# 4_PowerSupplie.net
KiCad netlist of a schematic drawn in Altium Designer
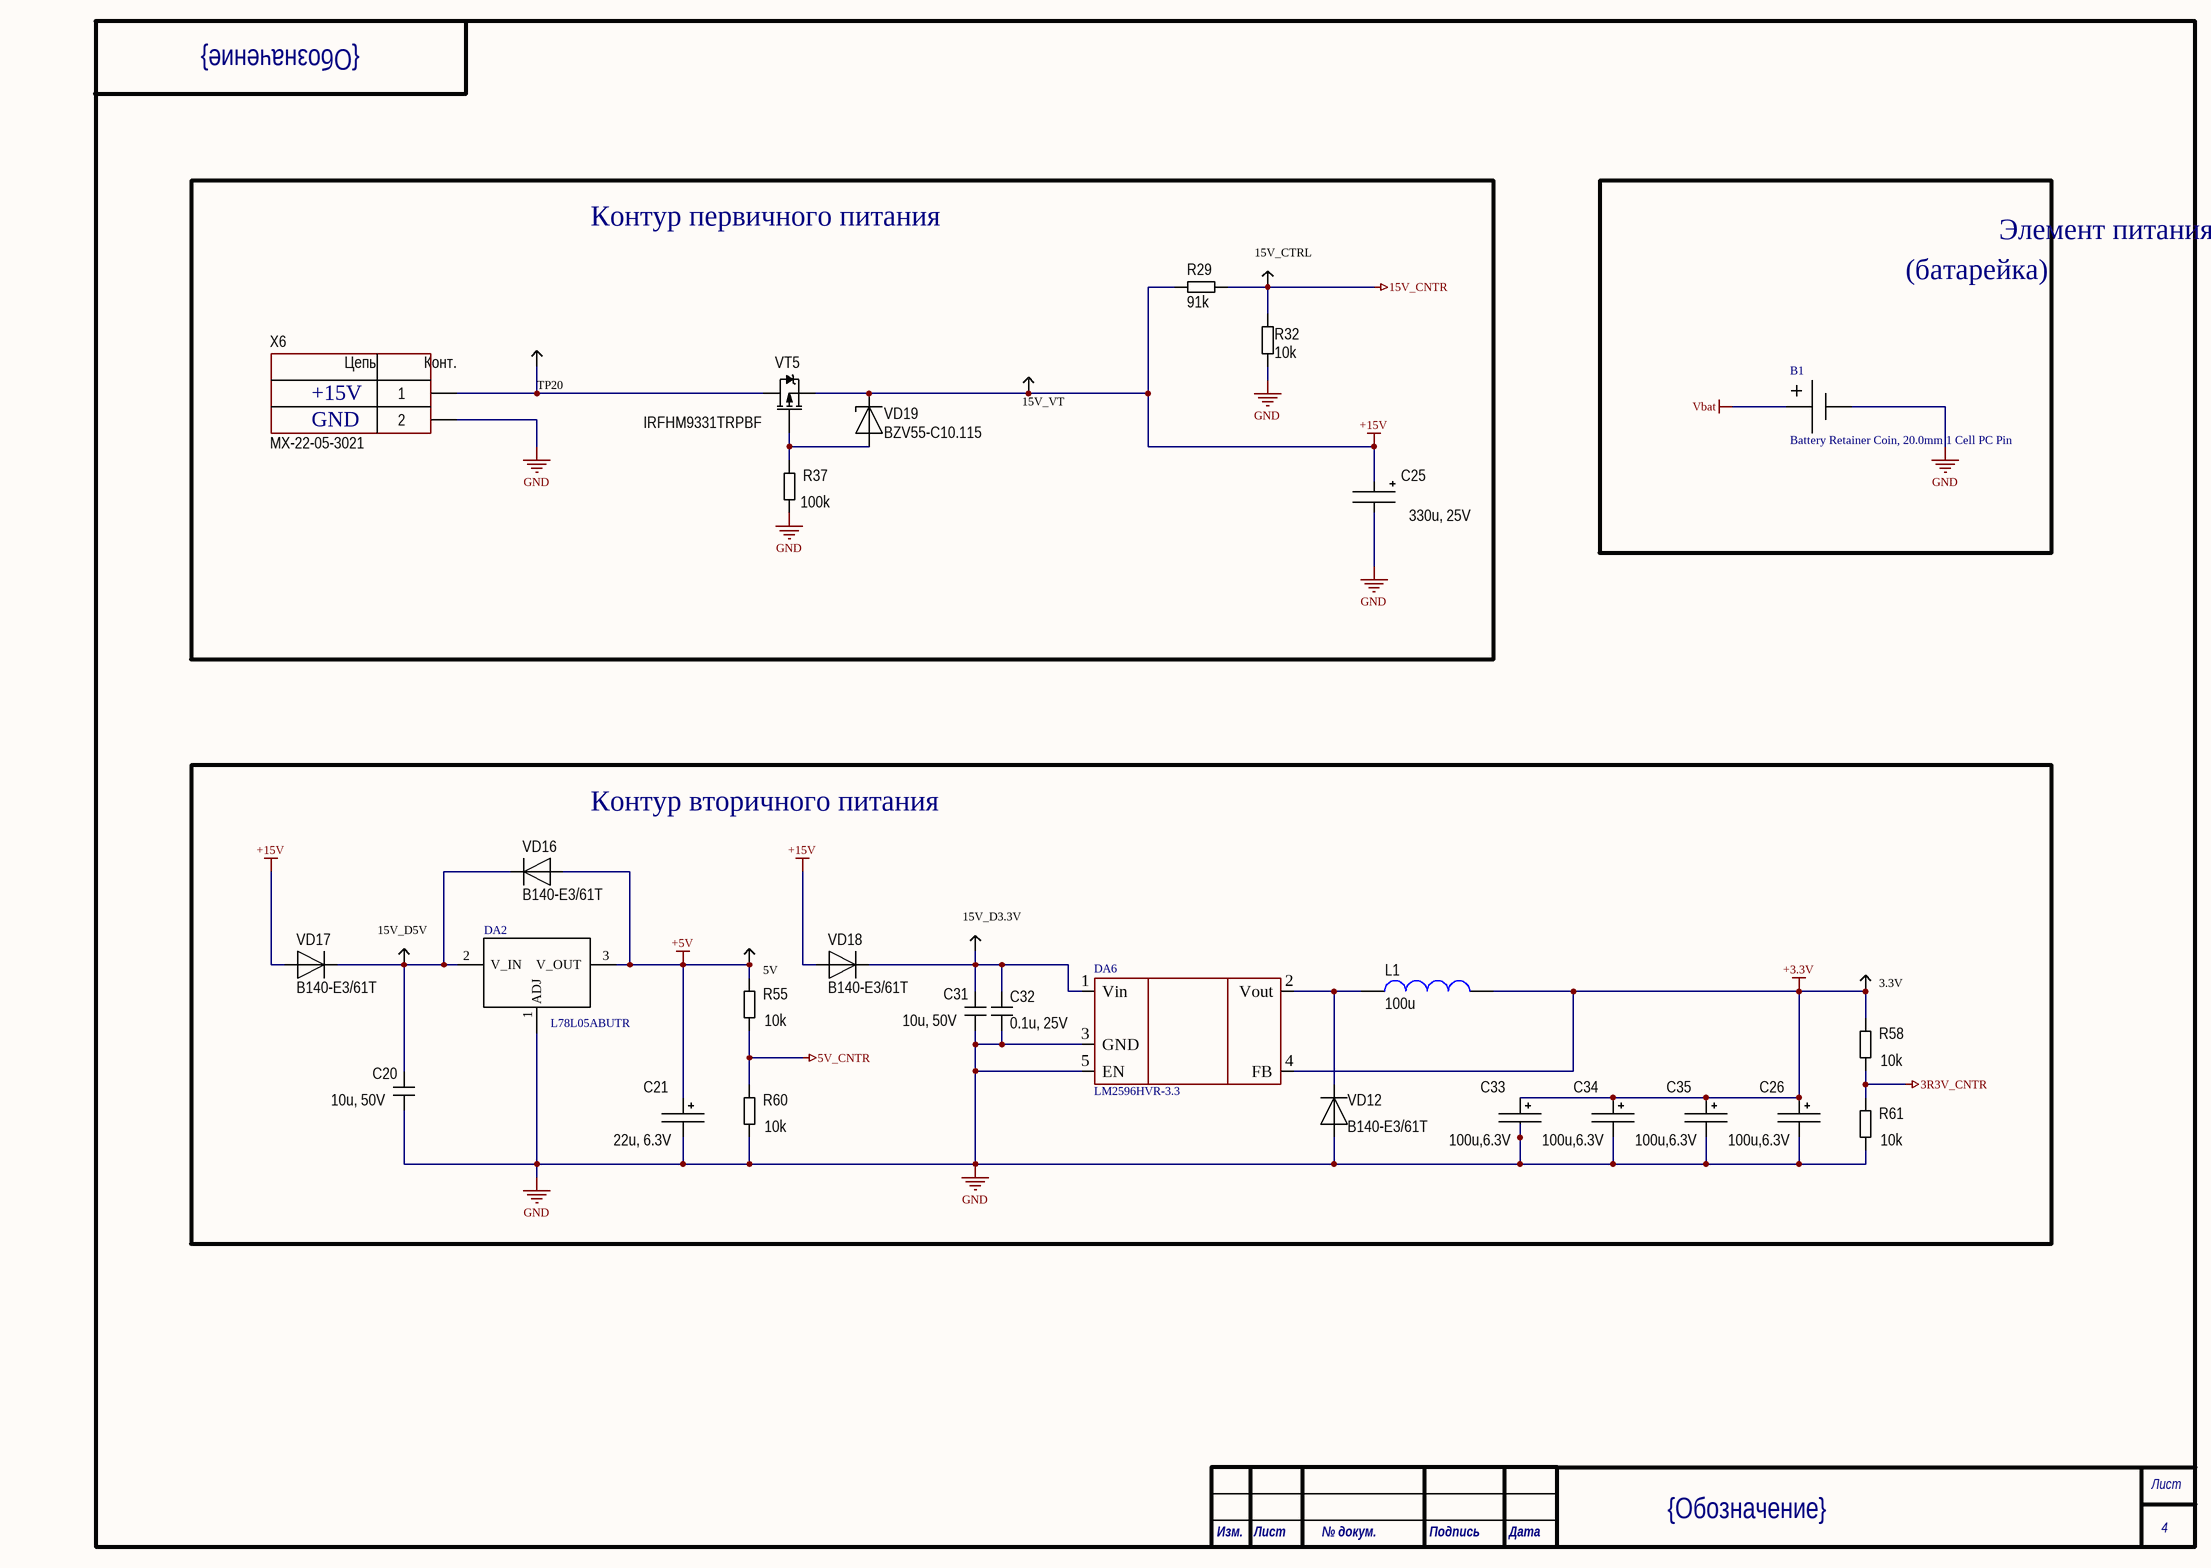
[diagram p0: 4_PowerSupplie.SchDoc]

(export (version "E")
  (design (tool "Eeschema 10.0.6"))
  (components
    (comp (ref "3.3V") (value "~") (footprint "TestPoint") (libsource (lib "Melochi") (part "TestPoint")))
    (comp (ref "5V") (value "~") (footprint "TestPoint") (libsource (lib "Melochi") (part "TestPoint")))
    (comp (ref "15V_CTRL") (value "~") (footprint "TestPoint") (libsource (lib "Melochi") (part "TestPoint")))
    (comp (ref "15V_D3.3V")
      (value "~")
      (footprint "TestPoint")
      (libsource (lib "Melochi") (part "TestPoint"))
    )
    (comp (ref "15V_D5V") (value "~") (footprint "TestPoint") (libsource (lib "Melochi") (part "TestPoint")))
    (comp (ref "15V_VT") (value "~") (footprint "TestPoint") (libsource (lib "Melochi") (part "TestPoint")))
    (comp (ref "B1")
      (value "Battery Retainer Coin, 20.0mm 1 Cell PC Pin")
      (footprint "BAT: CR2032_SM")
      (description "Battery Retainer Coin, 20.0mm 1 Cell PC Pin, Keystone Electronics")
      (libsource (lib "Melochi") (part "Battery_CR2032"))
    )
    (comp (ref "C20")
      (value "10u, 50V")
      (footprint "CH1206C")
      (libsource (lib "Condensators") (part "Capacitor"))
    )
    (comp (ref "C21")
      (value "22u, 6.3V")
      (footprint "TANTAL_A")
      (libsource (lib "Condensators") (part "TantalCap"))
    )
    (comp (ref "C25")
      (value "330u, 25V")
      (footprint "D10C4.4H10")
      (libsource (lib "Condensators") (part "AlumCap"))
    )
    (comp (ref "C26")
      (value "100u,6.3V")
      (footprint "TANTAL_C")
      (libsource (lib "Condensators") (part "TantalCap"))
    )
    (comp (ref "C31")
      (value "10u, 50V")
      (footprint "CH1206C")
      (libsource (lib "Condensators") (part "Capacitor"))
    )
    (comp (ref "C32")
      (value "0.1u, 25V")
      (footprint "CH0603C")
      (libsource (lib "Condensators") (part "Capacitor"))
    )
    (comp (ref "C33")
      (value "100u,6.3V")
      (footprint "TANTAL_C")
      (libsource (lib "Condensators") (part "TantalCap"))
    )
    (comp (ref "C34")
      (value "100u,6.3V")
      (footprint "TANTAL_C")
      (libsource (lib "Condensators") (part "TantalCap"))
    )
    (comp (ref "C35")
      (value "100u,6.3V")
      (footprint "TANTAL_C")
      (libsource (lib "Condensators") (part "TantalCap"))
    )
    (comp (ref "DA2")
      (value "L78L05ABUTR")
      (footprint "SOT89_PC12120")
      (libsource (lib "MicroIC") (part "LM1117"))
    )
    (comp (ref "DA6")
      (value "LM2596HVR-3.3")
      (footprint "TO263S-5+1")
      (libsource (lib "MicroIC") (part "LM2575HV"))
    )
    (comp (ref "L1")
      (value "100u")
      (footprint "IND: B82477G4")
      (libsource (lib "Inductance") (part "Inductor"))
    )
    (comp (ref "R29") (value "91k") (footprint "CH0402R") (libsource (lib "Resistors") (part "Resistor")))
    (comp (ref "R32") (value "10k") (footprint "CH0402R") (libsource (lib "Resistors") (part "Resistor")))
    (comp (ref "R37") (value "100k") (footprint "CH0402R") (libsource (lib "Resistors") (part "Resistor")))
    (comp (ref "R55") (value "10k") (footprint "CH0402R") (libsource (lib "Resistors") (part "Resistor")))
    (comp (ref "R58") (value "10k") (footprint "CH0402R") (libsource (lib "Resistors") (part "Resistor")))
    (comp (ref "R60") (value "10k") (footprint "CH0402R") (libsource (lib "Resistors") (part "Resistor")))
    (comp (ref "R61") (value "10k") (footprint "CH0402R") (libsource (lib "Resistors") (part "Resistor")))
    (comp (ref "TP20") (value "~") (footprint "TestPoint") (libsource (lib "Melochi") (part "TestPoint")))
    (comp (ref "VD12") (value "B140-E3/61T") (footprint "SMA") (libsource (lib "Diods") (part "Diod")))
    (comp (ref "VD16") (value "B140-E3/61T") (footprint "SMA") (libsource (lib "Diods") (part "Diod")))
    (comp (ref "VD17") (value "B140-E3/61T") (footprint "SMA") (libsource (lib "Diods") (part "Diod")))
    (comp (ref "VD18") (value "B140-E3/61T") (footprint "SMA") (libsource (lib "Diods") (part "Diod")))
    (comp (ref "VD19")
      (value "BZV55-C10.115")
      (footprint "SOD80")
      (libsource (lib "Diods") (part "Diod Zener"))
    )
    (comp (ref "VT5")
      (value "IRFHM9331TRPBF")
      (footprint "PQFN-3x3")
      (description "Mosfet")
      (libsource (lib "Tranzistor") (part "P-chanel"))
    )
    (comp (ref "X6")
      (value "MX-22-05-3021")
      (footprint "CON: MX-22-05-3021")
      (libsource (lib "Connectors") (part "2-Connector"))
    )
  )
  (nets
    (net (code "1") (name "+3.3V") (class "Default")
      (node (ref "3.3V") (pin "0") (pinfunction "0_0") (pintype "passive"))
      (node (ref "C26") (pin "1") (pinfunction "1_1") (pintype "power_in"))
      (node (ref "C33") (pin "1") (pinfunction "1_1") (pintype "power_in"))
      (node (ref "C34") (pin "1") (pinfunction "1_1") (pintype "power_in"))
      (node (ref "C35") (pin "1") (pinfunction "1_1") (pintype "power_in"))
      (node (ref "DA6") (pin "4") (pinfunction "FB_4") (pintype "passive"))
      (node (ref "L1") (pin "1") (pinfunction "1_1") (pintype "passive"))
      (node (ref "R58") (pin "2") (pinfunction "2_2") (pintype "passive"))
    )
    (net (code "2") (name "+5V") (class "Default")
      (node (ref "5V") (pin "0") (pinfunction "0_0") (pintype "passive"))
      (node (ref "C21") (pin "1") (pinfunction "1_1") (pintype "power_in"))
      (node (ref "DA2") (pin "3") (pinfunction "V_OUT_3") (pintype "passive"))
      (node (ref "R55") (pin "2") (pinfunction "2_2") (pintype "passive"))
      (node (ref "VD16") (pin "1") (pinfunction "1_1") (pintype "passive"))
    )
    (net (code "3") (name "+15V") (class "Default")
      (node (ref "15V_VT") (pin "0") (pinfunction "0_0") (pintype "passive"))
      (node (ref "C25") (pin "1") (pinfunction "1_1") (pintype "power_in"))
      (node (ref "R29") (pin "2") (pinfunction "2_2") (pintype "passive"))
      (node (ref "VD17") (pin "1") (pinfunction "1_1") (pintype "passive"))
      (node (ref "VD18") (pin "1") (pinfunction "1_1") (pintype "passive"))
      (node (ref "VD19") (pin "2") (pinfunction "C_2") (pintype "passive"))
      (node (ref "VT5") (pin "3") (pinfunction "S_3") (pintype "passive"))
    )
    (net (code "4") (name "3R3V_CNTR") (class "Default")
      (node (ref "R58") (pin "1") (pinfunction "1_1") (pintype "passive"))
      (node (ref "R61") (pin "2") (pinfunction "2_2") (pintype "passive"))
    )
    (net (code "5") (name "5V_CNTR") (class "Default")
      (node (ref "R55") (pin "1") (pinfunction "1_1") (pintype "passive"))
      (node (ref "R60") (pin "2") (pinfunction "2_2") (pintype "passive"))
    )
    (net (code "6") (name "15V_CNTR") (class "Default")
      (node (ref "15V_CTRL") (pin "0") (pinfunction "0_0") (pintype "passive"))
      (node (ref "R29") (pin "1") (pinfunction "1_1") (pintype "passive"))
      (node (ref "R32") (pin "1") (pinfunction "1_1") (pintype "passive"))
    )
    (net (code "7") (name "GND") (class "Default")
      (node (ref "B1") (pin "2") (pinfunction "2_2") (pintype "passive"))
      (node (ref "C20") (pin "1") (pinfunction "1_1") (pintype "passive"))
      (node (ref "C21") (pin "2") (pinfunction "2_2") (pintype "power_in"))
      (node (ref "C25") (pin "2") (pinfunction "2_2") (pintype "power_in"))
      (node (ref "C26") (pin "2") (pinfunction "2_2") (pintype "power_in"))
      (node (ref "C31") (pin "1") (pinfunction "1_1") (pintype "passive"))
      (node (ref "C32") (pin "1") (pinfunction "1_1") (pintype "passive"))
      (node (ref "C33") (pin "2") (pinfunction "2_2") (pintype "power_in"))
      (node (ref "C34") (pin "2") (pinfunction "2_2") (pintype "power_in"))
      (node (ref "C35") (pin "2") (pinfunction "2_2") (pintype "power_in"))
      (node (ref "DA2") (pin "1") (pinfunction "ADJ_1") (pintype "passive"))
      (node (ref "DA6") (pin "3") (pinfunction "GND_3") (pintype "passive"))
      (node (ref "DA6") (pin "5") (pinfunction "EN_5") (pintype "passive"))
      (node (ref "R32") (pin "2") (pinfunction "2_2") (pintype "passive"))
      (node (ref "R37") (pin "1") (pinfunction "1_1") (pintype "passive"))
      (node (ref "R60") (pin "1") (pinfunction "1_1") (pintype "passive"))
      (node (ref "R61") (pin "1") (pinfunction "1_1") (pintype "passive"))
      (node (ref "VD12") (pin "1") (pinfunction "1_1") (pintype "passive"))
      (node (ref "X6") (pin "2") (pinfunction "2_2") (pintype "passive"))
    )
    (net (code "8") (name "Net-(DA2-V_IN)") (class "Default")
      (node (ref "15V_D5V") (pin "0") (pinfunction "0_0") (pintype "passive"))
      (node (ref "C20") (pin "2") (pinfunction "2_2") (pintype "passive"))
      (node (ref "DA2") (pin "2") (pinfunction "V_IN_2") (pintype "passive"))
      (node (ref "VD16") (pin "2") (pinfunction "2_2") (pintype "passive"))
      (node (ref "VD17") (pin "2") (pinfunction "2_2") (pintype "passive"))
    )
    (net (code "9") (name "Net-(DA6-Vin)") (class "Default")
      (node (ref "15V_D3.3V") (pin "0") (pinfunction "0_0") (pintype "passive"))
      (node (ref "C31") (pin "2") (pinfunction "2_2") (pintype "passive"))
      (node (ref "C32") (pin "2") (pinfunction "2_2") (pintype "passive"))
      (node (ref "DA6") (pin "1") (pinfunction "Vin_1") (pintype "passive"))
      (node (ref "VD18") (pin "2") (pinfunction "2_2") (pintype "passive"))
    )
    (net (code "10") (name "Net-(DA6-Vout)") (class "Default")
      (node (ref "DA6") (pin "2") (pinfunction "Vout_2") (pintype "passive"))
      (node (ref "L1") (pin "2") (pinfunction "2_2") (pintype "passive"))
      (node (ref "VD12") (pin "2") (pinfunction "2_2") (pintype "passive"))
    )
    (net (code "11") (name "Net-(VD19-A)") (class "Default")
      (node (ref "R37") (pin "2") (pinfunction "2_2") (pintype "passive"))
      (node (ref "VD19") (pin "1") (pinfunction "A_1") (pintype "passive"))
      (node (ref "VT5") (pin "1") (pinfunction "G_1") (pintype "passive"))
    )
    (net (code "12") (name "Net-(VT5-D)") (class "Default")
      (node (ref "TP20") (pin "0") (pinfunction "0_0") (pintype "passive"))
      (node (ref "VT5") (pin "2") (pinfunction "D_2") (pintype "passive"))
      (node (ref "X6") (pin "1") (pinfunction "1_1") (pintype "passive"))
    )
    (net (code "13") (name "Vbat") (class "Default")
      (node (ref "B1") (pin "1") (pinfunction "1_1") (pintype "passive"))
    )
  )
)
